# Audio_Power.net
KiCad netlist of a schematic drawn in Altium Designer
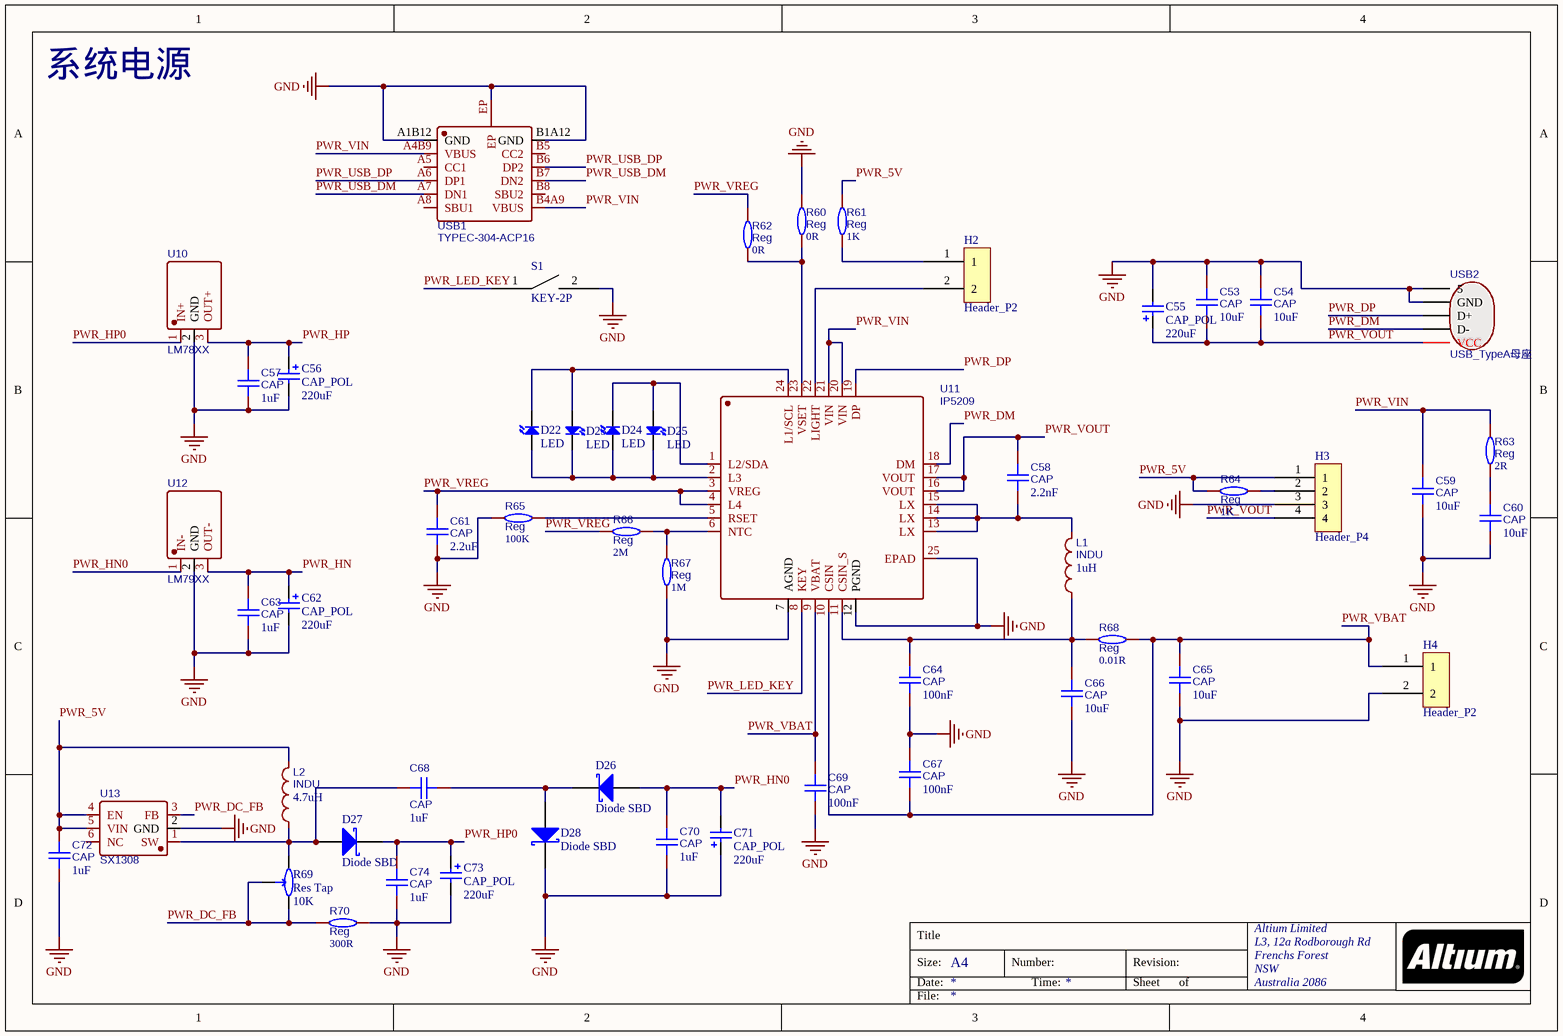
[diagram p0: Audio_Power.SchDoc]

(export (version "E")
  (design (tool "Eeschema 10.0.6"))
  (components
    (comp (ref "C53")
      (value "CAP")
      (footprint "C0603")
      (description "Cap")
      (fields
        (field (name "BOM_SUPPLIER PART") "C302008")
        (field (name "BOM_MANUFACTURER PART") "0603B103K101CT")
        (field (name "ALTIUM_VALUE") "10uF")
        (field (name "CONTRIBUTOR") "LCSC")
      )
      (libsource (lib "Levent_lib") (part "CAP"))
    )
    (comp (ref "C54")
      (value "CAP")
      (footprint "C0603")
      (description "Cap")
      (fields
        (field (name "BOM_SUPPLIER PART") "C302008")
        (field (name "BOM_MANUFACTURER PART") "0603B103K101CT")
        (field (name "ALTIUM_VALUE") "10uF")
        (field (name "CONTRIBUTOR") "LCSC")
      )
      (libsource (lib "Levent_lib") (part "CAP"))
    )
    (comp (ref "C55")
      (value "CAP_POL")
      (footprint "CAP_SMD_6.3mm")
      (description "极性电容")
      (fields (field (name "ALTIUM_VALUE") "220uF"))
      (libsource (lib "Levent_lib") (part "CAP_POL"))
    )
    (comp (ref "C56")
      (value "CAP_POL")
      (footprint "CAP_SMD_6.3mm")
      (description "极性电容")
      (fields (field (name "ALTIUM_VALUE") "220uF"))
      (libsource (lib "Levent_lib") (part "CAP_POL"))
    )
    (comp (ref "C57")
      (value "CAP")
      (footprint "C0603")
      (description "Cap")
      (fields
        (field (name "BOM_SUPPLIER PART") "C302008")
        (field (name "BOM_MANUFACTURER PART") "0603B103K101CT")
        (field (name "ALTIUM_VALUE") "1uF")
        (field (name "CONTRIBUTOR") "LCSC")
      )
      (libsource (lib "Levent_lib") (part "CAP"))
    )
    (comp (ref "C58")
      (value "CAP")
      (footprint "C0603")
      (description "Cap")
      (fields
        (field (name "BOM_SUPPLIER PART") "C302008")
        (field (name "BOM_MANUFACTURER PART") "0603B103K101CT")
        (field (name "ALTIUM_VALUE") "2.2nF")
        (field (name "CONTRIBUTOR") "LCSC")
      )
      (libsource (lib "Levent_lib") (part "CAP"))
    )
    (comp (ref "C59")
      (value "CAP")
      (footprint "C0603")
      (description "Cap")
      (fields
        (field (name "BOM_SUPPLIER PART") "C302008")
        (field (name "BOM_MANUFACTURER PART") "0603B103K101CT")
        (field (name "ALTIUM_VALUE") "10uF")
        (field (name "CONTRIBUTOR") "LCSC")
      )
      (libsource (lib "Levent_lib") (part "CAP"))
    )
    (comp (ref "C60")
      (value "CAP")
      (footprint "C0603")
      (description "Cap")
      (fields
        (field (name "BOM_SUPPLIER PART") "C302008")
        (field (name "BOM_MANUFACTURER PART") "0603B103K101CT")
        (field (name "ALTIUM_VALUE") "10uF")
        (field (name "CONTRIBUTOR") "LCSC")
      )
      (libsource (lib "Levent_lib") (part "CAP"))
    )
    (comp (ref "C61")
      (value "CAP")
      (footprint "C0603")
      (description "Cap")
      (fields
        (field (name "BOM_SUPPLIER PART") "C302008")
        (field (name "BOM_MANUFACTURER PART") "0603B103K101CT")
        (field (name "ALTIUM_VALUE") "2.2uF")
        (field (name "CONTRIBUTOR") "LCSC")
      )
      (libsource (lib "Levent_lib") (part "CAP"))
    )
    (comp (ref "C62")
      (value "CAP_POL")
      (footprint "CAP_SMD_6.3mm")
      (description "极性电容")
      (fields (field (name "ALTIUM_VALUE") "220uF"))
      (libsource (lib "Levent_lib") (part "CAP_POL"))
    )
    (comp (ref "C63")
      (value "CAP")
      (footprint "C0603")
      (description "Cap")
      (fields
        (field (name "BOM_SUPPLIER PART") "C302008")
        (field (name "BOM_MANUFACTURER PART") "0603B103K101CT")
        (field (name "ALTIUM_VALUE") "1uF")
        (field (name "CONTRIBUTOR") "LCSC")
      )
      (libsource (lib "Levent_lib") (part "CAP"))
    )
    (comp (ref "C64")
      (value "CAP")
      (footprint "C0603")
      (description "Cap")
      (fields
        (field (name "BOM_SUPPLIER PART") "C302008")
        (field (name "BOM_MANUFACTURER PART") "0603B103K101CT")
        (field (name "ALTIUM_VALUE") "100nF")
        (field (name "CONTRIBUTOR") "LCSC")
      )
      (libsource (lib "Levent_lib") (part "CAP"))
    )
    (comp (ref "C65")
      (value "CAP")
      (footprint "C0603")
      (description "Cap")
      (fields
        (field (name "BOM_SUPPLIER PART") "C302008")
        (field (name "BOM_MANUFACTURER PART") "0603B103K101CT")
        (field (name "ALTIUM_VALUE") "10uF")
        (field (name "CONTRIBUTOR") "LCSC")
      )
      (libsource (lib "Levent_lib") (part "CAP"))
    )
    (comp (ref "C66")
      (value "CAP")
      (footprint "C0603")
      (description "Cap")
      (fields
        (field (name "BOM_SUPPLIER PART") "C302008")
        (field (name "BOM_MANUFACTURER PART") "0603B103K101CT")
        (field (name "ALTIUM_VALUE") "10uF")
        (field (name "CONTRIBUTOR") "LCSC")
      )
      (libsource (lib "Levent_lib") (part "CAP"))
    )
    (comp (ref "C67")
      (value "CAP")
      (footprint "C0603")
      (description "Cap")
      (fields
        (field (name "BOM_SUPPLIER PART") "C302008")
        (field (name "BOM_MANUFACTURER PART") "0603B103K101CT")
        (field (name "ALTIUM_VALUE") "100nF")
        (field (name "CONTRIBUTOR") "LCSC")
      )
      (libsource (lib "Levent_lib") (part "CAP"))
    )
    (comp (ref "C68")
      (value "CAP")
      (footprint "C0603")
      (description "Cap")
      (fields
        (field (name "BOM_SUPPLIER PART") "C302008")
        (field (name "BOM_MANUFACTURER PART") "0603B103K101CT")
        (field (name "ALTIUM_VALUE") "1uF")
        (field (name "CONTRIBUTOR") "LCSC")
      )
      (libsource (lib "Levent_lib") (part "CAP"))
    )
    (comp (ref "C69")
      (value "CAP")
      (footprint "C0603")
      (description "Cap")
      (fields
        (field (name "BOM_SUPPLIER PART") "C302008")
        (field (name "BOM_MANUFACTURER PART") "0603B103K101CT")
        (field (name "ALTIUM_VALUE") "100nF")
        (field (name "CONTRIBUTOR") "LCSC")
      )
      (libsource (lib "Levent_lib") (part "CAP"))
    )
    (comp (ref "C70")
      (value "CAP")
      (footprint "C0603")
      (description "Cap")
      (fields
        (field (name "BOM_SUPPLIER PART") "C302008")
        (field (name "BOM_MANUFACTURER PART") "0603B103K101CT")
        (field (name "ALTIUM_VALUE") "1uF")
        (field (name "CONTRIBUTOR") "LCSC")
      )
      (libsource (lib "Levent_lib") (part "CAP"))
    )
    (comp (ref "C71")
      (value "CAP_POL")
      (footprint "CAP_SMD_6.3mm")
      (description "极性电容")
      (fields (field (name "ALTIUM_VALUE") "220uF"))
      (libsource (lib "Levent_lib") (part "CAP_POL"))
    )
    (comp (ref "C72")
      (value "CAP")
      (footprint "C0603")
      (description "Cap")
      (fields
        (field (name "BOM_SUPPLIER PART") "C302008")
        (field (name "BOM_MANUFACTURER PART") "0603B103K101CT")
        (field (name "ALTIUM_VALUE") "1uF")
        (field (name "CONTRIBUTOR") "LCSC")
      )
      (libsource (lib "Levent_lib") (part "CAP"))
    )
    (comp (ref "C73")
      (value "CAP_POL")
      (footprint "CAP_SMD_6.3mm")
      (description "极性电容")
      (fields (field (name "ALTIUM_VALUE") "220uF"))
      (libsource (lib "Levent_lib") (part "CAP_POL"))
    )
    (comp (ref "C74")
      (value "CAP")
      (footprint "C0603")
      (description "Cap")
      (fields
        (field (name "BOM_SUPPLIER PART") "C302008")
        (field (name "BOM_MANUFACTURER PART") "0603B103K101CT")
        (field (name "ALTIUM_VALUE") "1uF")
        (field (name "CONTRIBUTOR") "LCSC")
      )
      (libsource (lib "Levent_lib") (part "CAP"))
    )
    (comp (ref "D22")
      (value "LED")
      (footprint "LED0603_Side")
      (fields (field (name "PUBLISHER") "Altium Limited"))
      (libsource (lib "Levent_lib") (part "LED0"))
    )
    (comp (ref "D23")
      (value "LED")
      (footprint "LED0603_Side")
      (fields (field (name "PUBLISHER") "Altium Limited"))
      (libsource (lib "Levent_lib") (part "LED0"))
    )
    (comp (ref "D24")
      (value "LED")
      (footprint "LED0603_Side")
      (fields (field (name "PUBLISHER") "Altium Limited"))
      (libsource (lib "Levent_lib") (part "LED0"))
    )
    (comp (ref "D25")
      (value "LED")
      (footprint "LED0603_Side")
      (fields (field (name "PUBLISHER") "Altium Limited"))
      (libsource (lib "Levent_lib") (part "LED0"))
    )
    (comp (ref "D26")
      (value "Diode SBD")
      (footprint "SMA_L4.3")
      (description "Schottky Rectifier")
      (fields (field (name "PUBLISHER") "Altium Limited"))
      (libsource (lib "Levent_lib") (part "Diode SBD"))
    )
    (comp (ref "D27")
      (value "Diode SBD")
      (footprint "SMA_L4.3")
      (description "Schottky Rectifier")
      (fields (field (name "PUBLISHER") "Altium Limited"))
      (libsource (lib "Levent_lib") (part "Diode SBD"))
    )
    (comp (ref "D28")
      (value "Diode SBD")
      (footprint "SMA_L4.3")
      (description "Schottky Rectifier")
      (fields (field (name "PUBLISHER") "Altium Limited"))
      (libsource (lib "Levent_lib") (part "Diode SBD"))
    )
    (comp (ref "H2")
      (value "Header_P2")
      (footprint "H_2.54_P2")
      (description "2Pin排针")
      (libsource (lib "Levent_lib") (part "Header_P2"))
    )
    (comp (ref "H3")
      (value "Header_P4")
      (footprint "H_2.54_P4")
      (description "4Pin排针")
      (libsource (lib "Levent_lib") (part "Header_P4"))
    )
    (comp (ref "H4")
      (value "Header_P2")
      (footprint "H_2.54_P2")
      (description "2Pin排针")
      (libsource (lib "Levent_lib") (part "Header_P2"))
    )
    (comp (ref "L1")
      (value "INDU")
      (footprint "SMD_L7.1")
      (description "电感")
      (fields
        (field (name "BOM_SUPPLIER PART") "C182182")
        (field (name "BOM_MANUFACTURER PART") "SLO0630H150MTT")
        (field (name "ALTIUM_VALUE") "1uH")
        (field (name "CONTRIBUTOR") "LCSC")
      )
      (libsource (lib "Levent_lib") (part "IND"))
    )
    (comp (ref "L2")
      (value "INDU")
      (footprint "SMD_L7.1")
      (description "电感")
      (fields
        (field (name "BOM_SUPPLIER PART") "C182182")
        (field (name "BOM_MANUFACTURER PART") "SLO0630H150MTT")
        (field (name "ALTIUM_VALUE") "4.7uH")
        (field (name "CONTRIBUTOR") "LCSC")
      )
      (libsource (lib "Levent_lib") (part "IND"))
    )
    (comp (ref "R60")
      (value "Reg")
      (footprint "R0603")
      (description "电阻")
      (fields
        (field (name "BOM_SUPPLIER PART") "C465721")
        (field (name "BOM_MANUFACTURER PART") "AR03BTCX1002A")
        (field (name "ALTIUM_VALUE") "0R")
        (field (name "CONTRIBUTOR") "LCSC")
      )
      (libsource (lib "Levent_lib") (part "Res"))
    )
    (comp (ref "R61")
      (value "Reg")
      (footprint "R0603")
      (description "电阻")
      (fields
        (field (name "BOM_SUPPLIER PART") "C465721")
        (field (name "BOM_MANUFACTURER PART") "AR03BTCX1002A")
        (field (name "ALTIUM_VALUE") "1K")
        (field (name "CONTRIBUTOR") "LCSC")
      )
      (libsource (lib "Levent_lib") (part "Res"))
    )
    (comp (ref "R62")
      (value "Reg")
      (footprint "R0603")
      (description "电阻")
      (fields
        (field (name "BOM_SUPPLIER PART") "C465721")
        (field (name "BOM_MANUFACTURER PART") "AR03BTCX1002A")
        (field (name "ALTIUM_VALUE") "0R")
        (field (name "CONTRIBUTOR") "LCSC")
      )
      (libsource (lib "Levent_lib") (part "Res"))
    )
    (comp (ref "R63")
      (value "Reg")
      (footprint "R0603")
      (description "电阻")
      (fields
        (field (name "BOM_SUPPLIER PART") "C465721")
        (field (name "BOM_MANUFACTURER PART") "AR03BTCX1002A")
        (field (name "ALTIUM_VALUE") "2R")
        (field (name "CONTRIBUTOR") "LCSC")
      )
      (libsource (lib "Levent_lib") (part "Res"))
    )
    (comp (ref "R64")
      (value "Reg")
      (footprint "R0603")
      (description "电阻")
      (fields
        (field (name "BOM_SUPPLIER PART") "C465721")
        (field (name "BOM_MANUFACTURER PART") "AR03BTCX1002A")
        (field (name "ALTIUM_VALUE") "1K")
        (field (name "CONTRIBUTOR") "LCSC")
      )
      (libsource (lib "Levent_lib") (part "Res"))
    )
    (comp (ref "R65")
      (value "Reg")
      (footprint "R0603")
      (description "电阻")
      (fields
        (field (name "BOM_SUPPLIER PART") "C465721")
        (field (name "BOM_MANUFACTURER PART") "AR03BTCX1002A")
        (field (name "ALTIUM_VALUE") "100K")
        (field (name "CONTRIBUTOR") "LCSC")
      )
      (libsource (lib "Levent_lib") (part "Res"))
    )
    (comp (ref "R66")
      (value "Reg")
      (footprint "R0603")
      (description "电阻")
      (fields
        (field (name "BOM_SUPPLIER PART") "C465721")
        (field (name "BOM_MANUFACTURER PART") "AR03BTCX1002A")
        (field (name "ALTIUM_VALUE") "2M")
        (field (name "CONTRIBUTOR") "LCSC")
      )
      (libsource (lib "Levent_lib") (part "Res"))
    )
    (comp (ref "R67")
      (value "Reg")
      (footprint "R0603")
      (description "电阻")
      (fields
        (field (name "BOM_SUPPLIER PART") "C465721")
        (field (name "BOM_MANUFACTURER PART") "AR03BTCX1002A")
        (field (name "ALTIUM_VALUE") "1M")
        (field (name "CONTRIBUTOR") "LCSC")
      )
      (libsource (lib "Levent_lib") (part "Res"))
    )
    (comp (ref "R68")
      (value "Reg")
      (footprint "R1206")
      (description "电阻")
      (fields
        (field (name "BOM_SUPPLIER PART") "C465721")
        (field (name "BOM_MANUFACTURER PART") "AR03BTCX1002A")
        (field (name "ALTIUM_VALUE") "0.01R")
        (field (name "CONTRIBUTOR") "LCSC")
      )
      (libsource (lib "Levent_lib") (part "Res"))
    )
    (comp (ref "R69")
      (value "Res Tap")
      (footprint "RES_TAP_HOR")
      (description "可调电阻")
      (fields (field (name "ALTIUM_VALUE") "10K") (field (name "PUBLISHER") "Altium Limited"))
      (libsource (lib "Levent_lib") (part "Res Tap"))
    )
    (comp (ref "R70")
      (value "Reg")
      (footprint "R0603")
      (description "电阻")
      (fields
        (field (name "BOM_SUPPLIER PART") "C465721")
        (field (name "BOM_MANUFACTURER PART") "AR03BTCX1002A")
        (field (name "ALTIUM_VALUE") "300R")
        (field (name "CONTRIBUTOR") "LCSC")
      )
      (libsource (lib "Levent_lib") (part "Res"))
    )
    (comp (ref "S1")
      (value "KEY-2P")
      (footprint "KEY_SOT_P2")
      (description "KEY-2Pp")
      (libsource (lib "Levent_lib") (part "KEY_2P"))
    )
    (comp (ref "U10")
      (value "LM78XX")
      (footprint "TO-220-3_2.54")
      (description "三端稳压(正电压)")
      (fields
        (field (name "BOM_SUPPLIER PART") "C2902509")
        (field (name "BOM_MANUFACTURER PART") "LM7812T")
        (field (name "CONTRIBUTOR") "LCSC")
      )
      (libsource (lib "Levent_lib") (part "LM78XX"))
    )
    (comp (ref "U11")
      (value "IP5209")
      (footprint "QFN-24")
      (description "USB充电宝")
      (fields (field (name "BOM_SUPPLIER PART") "C181695") (field (name "CONTRIBUTOR") "LCSC"))
      (libsource (lib "Levent_lib") (part "IP5209"))
    )
    (comp (ref "U12")
      (value "LM79XX")
      (footprint "TO-220-3_2.54")
      (description "三端稳压(负电压)")
      (fields
        (field (name "BOM_SUPPLIER PART") "C2902509")
        (field (name "BOM_MANUFACTURER PART") "LM7812T")
        (field (name "CONTRIBUTOR") "LCSC")
      )
      (libsource (lib "Levent_lib") (part "LM79XX"))
    )
    (comp (ref "U13")
      (value "SX1308")
      (footprint "SOT-23-6")
      (description "升压PWM")
      (fields (field (name "BOM_SUPPLIER PART") "C78162"))
      (libsource (lib "Levent_lib") (part "SX1308"))
    )
    (comp (ref "USB1")
      (value "TYPEC-304-ACP16")
      (footprint "USB-C-SMD_TYPE-C-16P")
      (description "全引脚USB TYPEC母座")
      (fields (field (name "BOM_SUPPLIER PART") "C2982555") (field (name "CONTRIBUTOR") "LCSC"))
      (libsource (lib "Levent_lib") (part "USB_TYPEC_12P"))
    )
    (comp (ref "USB2")
      (value "USB_TypeA母座")
      (footprint "USB_TYPEA-SMD")
      (fields
        (field (name "BOM_MANUFACTURER PART") "YJ-USB-AF-SMT-01")
        (field (name "BOM_SUPPLIER PART") "C8328")
      )
      (libsource (lib "Levent_lib") (part "USB-TYPEA"))
    )
  )
  (nets
    (net (code "1") (name "/PWR_5V") (class "Default")
      (node (ref "C72") (pin "1") (pinfunction "1_1") (pintype "passive"))
      (node (ref "H3") (pin "1") (pinfunction "1_1") (pintype "passive"))
      (node (ref "L2") (pin "2") (pinfunction "2_2") (pintype "passive"))
      (node (ref "R61") (pin "2") (pinfunction "2_2") (pintype "passive"))
      (node (ref "R64") (pin "1") (pinfunction "1_1") (pintype "passive"))
      (node (ref "U13") (pin "4") (pinfunction "EN_4") (pintype "passive"))
      (node (ref "U13") (pin "5") (pinfunction "VIN_5") (pintype "passive"))
    )
    (net (code "2") (name "/PWR_DC_FB") (class "Default")
      (node (ref "R69") (pin "1") (pinfunction "A_1") (pintype "passive"))
      (node (ref "R69") (pin "3") (pinfunction "TAP_3") (pintype "passive"))
      (node (ref "R70") (pin "1") (pinfunction "1_1") (pintype "passive"))
      (node (ref "U13") (pin "3") (pinfunction "FB_3") (pintype "passive"))
    )
    (net (code "3") (name "/PWR_DM") (class "Default")
      (node (ref "U11") (pin "18") (pinfunction "DM_18") (pintype "passive"))
      (node (ref "USB2") (pin "2") (pinfunction "D-_2") (pintype "passive"))
    )
    (net (code "4") (name "/PWR_DP") (class "Default")
      (node (ref "U11") (pin "19") (pinfunction "DP_19") (pintype "passive"))
      (node (ref "USB2") (pin "3") (pinfunction "D+_3") (pintype "passive"))
    )
    (net (code "5") (name "/PWR_HN") (class "Default")
      (node (ref "C62") (pin "1") (pinfunction "1_1") (pintype "passive"))
      (node (ref "C63") (pin "1") (pinfunction "1_1") (pintype "passive"))
      (node (ref "U12") (pin "3") (pinfunction "OUT-_3") (pintype "passive"))
    )
    (net (code "6") (name "/PWR_HN0") (class "Default")
      (node (ref "C70") (pin "1") (pinfunction "1_1") (pintype "passive"))
      (node (ref "C71") (pin "2") (pinfunction "2_2") (pintype "passive"))
      (node (ref "D26") (pin "2") (pinfunction "A_2") (pintype "passive"))
      (node (ref "U12") (pin "1") (pinfunction "IN-_1") (pintype "passive"))
    )
    (net (code "7") (name "/PWR_HP") (class "Default")
      (node (ref "C56") (pin "1") (pinfunction "1_1") (pintype "passive"))
      (node (ref "C57") (pin "1") (pinfunction "1_1") (pintype "passive"))
      (node (ref "U10") (pin "3") (pinfunction "OUT+_3") (pintype "passive"))
    )
    (net (code "8") (name "/PWR_HP0") (class "Default")
      (node (ref "C73") (pin "1") (pinfunction "1_1") (pintype "passive"))
      (node (ref "C74") (pin "1") (pinfunction "1_1") (pintype "passive"))
      (node (ref "D27") (pin "1") (pinfunction "K_1") (pintype "passive"))
      (node (ref "U10") (pin "1") (pinfunction "IN+_1") (pintype "passive"))
    )
    (net (code "9") (name "/PWR_LED_KEY") (class "Default")
      (node (ref "S1") (pin "1") (pinfunction "1_1") (pintype "passive"))
      (node (ref "U11") (pin "8") (pinfunction "KEY_8") (pintype "passive"))
    )
    (net (code "10") (name "/PWR_USB_DM") (class "Default")
      (node (ref "USB1") (pin "A7") (pinfunction "DN1_A7") (pintype "passive"))
      (node (ref "USB1") (pin "B7") (pinfunction "DN2_B7") (pintype "passive"))
    )
    (net (code "11") (name "/PWR_USB_DP") (class "Default")
      (node (ref "USB1") (pin "A6") (pinfunction "DP1_A6") (pintype "passive"))
      (node (ref "USB1") (pin "B6") (pinfunction "DP2_B6") (pintype "passive"))
    )
    (net (code "12") (name "/PWR_VBAT") (class "Default")
      (node (ref "C65") (pin "1") (pinfunction "1_1") (pintype "passive"))
      (node (ref "C67") (pin "2") (pinfunction "2_2") (pintype "passive"))
      (node (ref "C69") (pin "1") (pinfunction "1_1") (pintype "passive"))
      (node (ref "H4") (pin "1") (pinfunction "1_1") (pintype "passive"))
      (node (ref "R68") (pin "2") (pinfunction "2_2") (pintype "passive"))
      (node (ref "U11") (pin "10") (pinfunction "CSIN_10") (pintype "passive"))
      (node (ref "U11") (pin "9") (pinfunction "VBAT_9") (pintype "passive"))
    )
    (net (code "13") (name "/PWR_VIN") (class "Default")
      (node (ref "C59") (pin "1") (pinfunction "1_1") (pintype "passive"))
      (node (ref "R63") (pin "2") (pinfunction "2_2") (pintype "passive"))
      (node (ref "U11") (pin "20") (pinfunction "VIN_20") (pintype "passive"))
      (node (ref "U11") (pin "21") (pinfunction "VIN_21") (pintype "passive"))
      (node (ref "USB1") (pin "A4B9") (pinfunction "VBUS_A4B9") (pintype "passive"))
      (node (ref "USB1") (pin "B4A9") (pinfunction "VBUS_B4A9") (pintype "passive"))
    )
    (net (code "14") (name "/PWR_VOUT") (class "Default")
      (node (ref "C53") (pin "2") (pinfunction "2_2") (pintype "passive"))
      (node (ref "C54") (pin "2") (pinfunction "2_2") (pintype "passive"))
      (node (ref "C55") (pin "1") (pinfunction "1_1") (pintype "passive"))
      (node (ref "C58") (pin "1") (pinfunction "1_1") (pintype "passive"))
      (node (ref "H3") (pin "4") (pinfunction "4_4") (pintype "passive"))
      (node (ref "U11") (pin "16") (pinfunction "VOUT_16") (pintype "passive"))
      (node (ref "U11") (pin "17") (pinfunction "VOUT_17") (pintype "passive"))
      (node (ref "USB2") (pin "1") (pinfunction "VCC_1") (pintype "passive"))
    )
    (net (code "15") (name "/PWR_VREG") (class "Default")
      (node (ref "C61") (pin "1") (pinfunction "1_1") (pintype "passive"))
      (node (ref "R62") (pin "2") (pinfunction "2_2") (pintype "passive"))
      (node (ref "R66") (pin "2") (pinfunction "2_2") (pintype "passive"))
      (node (ref "U11") (pin "3") (pinfunction "VREG_3") (pintype "passive"))
      (node (ref "U11") (pin "4") (pinfunction "L4_4") (pintype "passive"))
    )
    (net (code "16") (name "GND") (class "Default")
      (node (ref "C53") (pin "1") (pinfunction "1_1") (pintype "passive"))
      (node (ref "C54") (pin "1") (pinfunction "1_1") (pintype "passive"))
      (node (ref "C55") (pin "2") (pinfunction "2_2") (pintype "passive"))
      (node (ref "C56") (pin "2") (pinfunction "2_2") (pintype "passive"))
      (node (ref "C57") (pin "2") (pinfunction "2_2") (pintype "passive"))
      (node (ref "C59") (pin "2") (pinfunction "2_2") (pintype "passive"))
      (node (ref "C60") (pin "2") (pinfunction "2_2") (pintype "passive"))
      (node (ref "C61") (pin "2") (pinfunction "2_2") (pintype "passive"))
      (node (ref "C62") (pin "2") (pinfunction "2_2") (pintype "passive"))
      (node (ref "C63") (pin "2") (pinfunction "2_2") (pintype "passive"))
      (node (ref "C64") (pin "2") (pinfunction "2_2") (pintype "passive"))
      (node (ref "C65") (pin "2") (pinfunction "2_2") (pintype "passive"))
      (node (ref "C66") (pin "2") (pinfunction "2_2") (pintype "passive"))
      (node (ref "C67") (pin "1") (pinfunction "1_1") (pintype "passive"))
      (node (ref "C69") (pin "2") (pinfunction "2_2") (pintype "passive"))
      (node (ref "C70") (pin "2") (pinfunction "2_2") (pintype "passive"))
      (node (ref "C71") (pin "1") (pinfunction "1_1") (pintype "passive"))
      (node (ref "C72") (pin "2") (pinfunction "2_2") (pintype "passive"))
      (node (ref "C73") (pin "2") (pinfunction "2_2") (pintype "passive"))
      (node (ref "C74") (pin "2") (pinfunction "2_2") (pintype "passive"))
      (node (ref "D28") (pin "1") (pinfunction "K_1") (pintype "passive"))
      (node (ref "H3") (pin "3") (pinfunction "3_3") (pintype "passive"))
      (node (ref "H4") (pin "2") (pinfunction "2_2") (pintype "passive"))
      (node (ref "R60") (pin "2") (pinfunction "2_2") (pintype "passive"))
      (node (ref "R65") (pin "2") (pinfunction "2_2") (pintype "passive"))
      (node (ref "R67") (pin "2") (pinfunction "2_2") (pintype "passive"))
      (node (ref "R70") (pin "2") (pinfunction "2_2") (pintype "passive"))
      (node (ref "S1") (pin "2") (pinfunction "2_2") (pintype "passive"))
      (node (ref "U10") (pin "2") (pinfunction "GND_2") (pintype "passive"))
      (node (ref "U11") (pin "12") (pinfunction "PGND_12") (pintype "passive"))
      (node (ref "U11") (pin "25") (pinfunction "EPAD_25") (pintype "passive"))
      (node (ref "U11") (pin "7") (pinfunction "AGND_7") (pintype "passive"))
      (node (ref "U12") (pin "2") (pinfunction "GND_2") (pintype "passive"))
      (node (ref "U13") (pin "2") (pinfunction "GND_2") (pintype "passive"))
      (node (ref "USB1") (pin "A1B12") (pinfunction "GND_A1B12") (pintype "passive"))
      (node (ref "USB1") (pin "B1A12") (pinfunction "GND_B1A12") (pintype "passive"))
      (node (ref "USB1") (pin "EP") (pinfunction "EP_EP") (pintype "passive"))
      (node (ref "USB2") (pin "4") (pinfunction "GND_4") (pintype "passive"))
      (node (ref "USB2") (pin "5") (pinfunction "5_5") (pintype "passive"))
    )
    (net (code "17") (name "Net-(C58-Pad2)") (class "Default")
      (node (ref "C58") (pin "2") (pinfunction "2_2") (pintype "passive"))
      (node (ref "L1") (pin "2") (pinfunction "2_2") (pintype "passive"))
      (node (ref "U11") (pin "13") (pinfunction "LX_13") (pintype "passive"))
      (node (ref "U11") (pin "14") (pinfunction "LX_14") (pintype "passive"))
      (node (ref "U11") (pin "15") (pinfunction "LX_15") (pintype "passive"))
    )
    (net (code "18") (name "Net-(C60-Pad1)") (class "Default")
      (node (ref "C60") (pin "1") (pinfunction "1_1") (pintype "passive"))
      (node (ref "R63") (pin "1") (pinfunction "1_1") (pintype "passive"))
    )
    (net (code "19") (name "Net-(D22-A)") (class "Default")
      (node (ref "D22") (pin "2") (pinfunction "A_2") (pintype "passive"))
      (node (ref "D23") (pin "1") (pinfunction "K_1") (pintype "passive"))
      (node (ref "D24") (pin "2") (pinfunction "A_2") (pintype "passive"))
      (node (ref "D25") (pin "1") (pinfunction "K_1") (pintype "passive"))
      (node (ref "U11") (pin "2") (pinfunction "L3_2") (pintype "passive"))
    )
    (net (code "20") (name "Net-(D22-K)") (class "Default")
      (node (ref "D22") (pin "1") (pinfunction "K_1") (pintype "passive"))
      (node (ref "D23") (pin "2") (pinfunction "A_2") (pintype "passive"))
      (node (ref "U11") (pin "24") (pinfunction "L1/SCL_24") (pintype "passive"))
    )
    (net (code "21") (name "Net-(D24-K)") (class "Default")
      (node (ref "D24") (pin "1") (pinfunction "K_1") (pintype "passive"))
      (node (ref "D25") (pin "2") (pinfunction "A_2") (pintype "passive"))
      (node (ref "U11") (pin "1") (pinfunction "L2/SDA_1") (pintype "passive"))
    )
    (net (code "22") (name "Net-(D26-K)") (class "Default")
      (node (ref "C68") (pin "2") (pinfunction "2_2") (pintype "passive"))
      (node (ref "D26") (pin "1") (pinfunction "K_1") (pintype "passive"))
      (node (ref "D28") (pin "2") (pinfunction "A_2") (pintype "passive"))
    )
    (net (code "23") (name "Net-(D27-A)") (class "Default")
      (node (ref "C68") (pin "1") (pinfunction "1_1") (pintype "passive"))
      (node (ref "D27") (pin "2") (pinfunction "A_2") (pintype "passive"))
      (node (ref "L2") (pin "1") (pinfunction "1_1") (pintype "passive"))
      (node (ref "R69") (pin "2") (pinfunction "B_2") (pintype "passive"))
      (node (ref "U13") (pin "1") (pinfunction "SW_1") (pintype "passive"))
    )
    (net (code "24") (name "Net-(H2-Pad1)") (class "Default")
      (node (ref "H2") (pin "1") (pinfunction "1_1") (pintype "passive"))
      (node (ref "R61") (pin "1") (pinfunction "1_1") (pintype "passive"))
    )
    (net (code "25") (name "Net-(H3-Pad2)") (class "Default")
      (node (ref "H3") (pin "2") (pinfunction "2_2") (pintype "passive"))
      (node (ref "R64") (pin "2") (pinfunction "2_2") (pintype "passive"))
    )
    (net (code "26") (name "Net-(U11-CSIN_S)") (class "Default")
      (node (ref "C64") (pin "1") (pinfunction "1_1") (pintype "passive"))
      (node (ref "C66") (pin "1") (pinfunction "1_1") (pintype "passive"))
      (node (ref "L1") (pin "1") (pinfunction "1_1") (pintype "passive"))
      (node (ref "R68") (pin "1") (pinfunction "1_1") (pintype "passive"))
      (node (ref "U11") (pin "11") (pinfunction "CSIN_S_11") (pintype "passive"))
    )
    (net (code "27") (name "Net-(U11-LIGHT)") (class "Default")
      (node (ref "H2") (pin "2") (pinfunction "2_2") (pintype "passive"))
      (node (ref "U11") (pin "22") (pinfunction "LIGHT_22") (pintype "passive"))
    )
    (net (code "28") (name "Net-(U11-NTC)") (class "Default")
      (node (ref "R66") (pin "1") (pinfunction "1_1") (pintype "passive"))
      (node (ref "R67") (pin "1") (pinfunction "1_1") (pintype "passive"))
      (node (ref "U11") (pin "6") (pinfunction "NTC_6") (pintype "passive"))
    )
    (net (code "29") (name "Net-(U11-RSET)") (class "Default")
      (node (ref "R65") (pin "1") (pinfunction "1_1") (pintype "passive"))
      (node (ref "U11") (pin "5") (pinfunction "RSET_5") (pintype "passive"))
    )
    (net (code "30") (name "Net-(U11-VSET)") (class "Default")
      (node (ref "R60") (pin "1") (pinfunction "1_1") (pintype "passive"))
      (node (ref "R62") (pin "1") (pinfunction "1_1") (pintype "passive"))
      (node (ref "U11") (pin "23") (pinfunction "VSET_23") (pintype "passive"))
    )
    (net (code "31") (name "unconnected-(U13-NC-Pad6)") (class "Default")
      (node (ref "U13") (pin "6") (pinfunction "NC_6") (pintype "passive"))
    )
    (net (code "32") (name "unconnected-(USB1-CC1-PadA5)") (class "Default")
      (node (ref "USB1") (pin "A5") (pinfunction "CC1_A5") (pintype "passive"))
    )
    (net (code "33") (name "unconnected-(USB1-CC2-PadB5)") (class "Default")
      (node (ref "USB1") (pin "B5") (pinfunction "CC2_B5") (pintype "passive"))
    )
    (net (code "34") (name "unconnected-(USB1-SBU1-PadA8)") (class "Default")
      (node (ref "USB1") (pin "A8") (pinfunction "SBU1_A8") (pintype "passive"))
    )
    (net (code "35") (name "unconnected-(USB1-SBU2-PadB8)") (class "Default")
      (node (ref "USB1") (pin "B8") (pinfunction "SBU2_B8") (pintype "passive"))
    )
  )
)
